# USB_Dongle_Parem.net
KiCad netlist of a schematic drawn in EAGLE
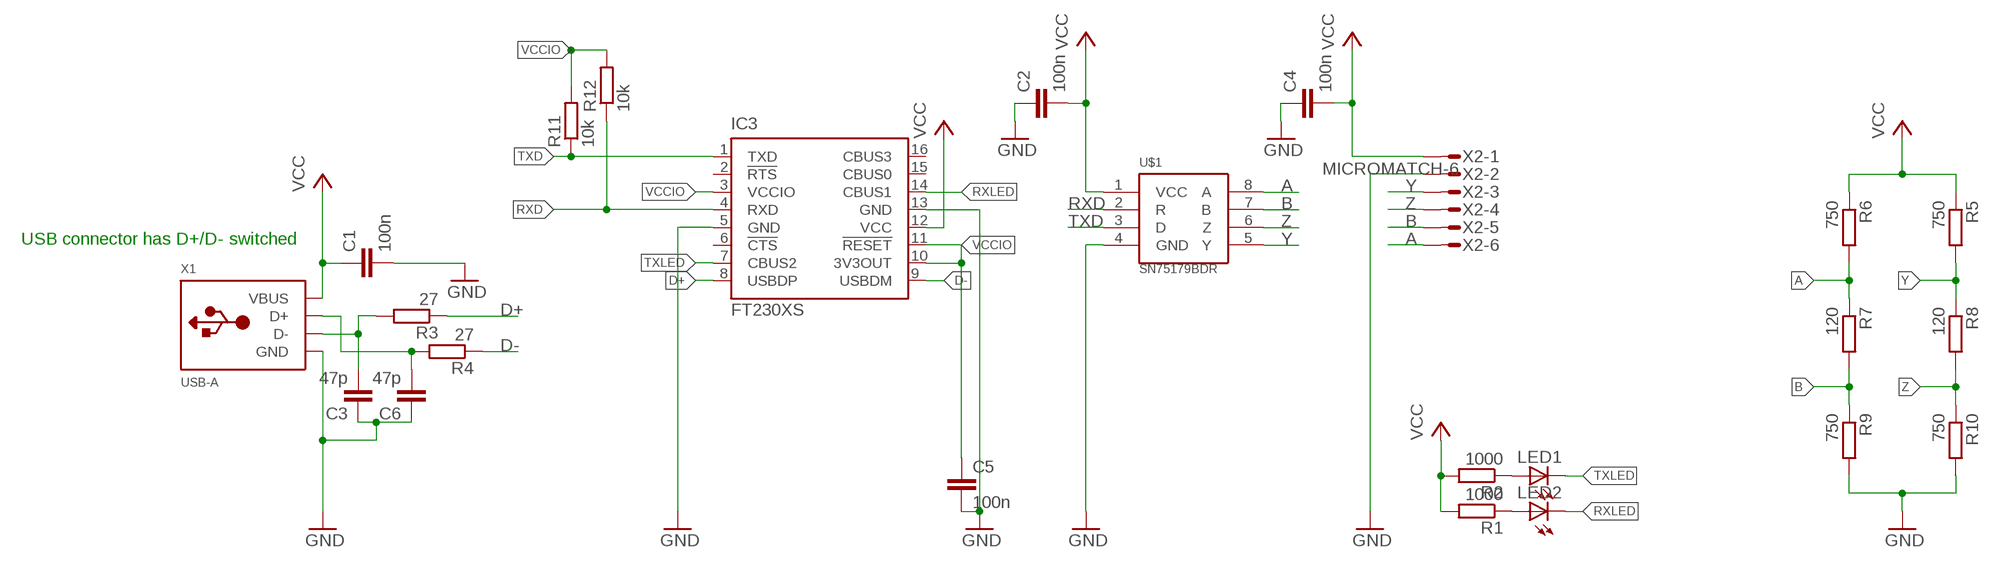
[diagram p0: schematic, sheet 1]

(export (version "E")
  (design (tool "Eeschema 10.0.6"))
  (components
    (comp (ref "C1")
      (value "100n")
      (footprint "eagle-import:C0603")
      (libsource (lib "eagle-import") (part "CC0603"))
    )
    (comp (ref "C2")
      (value "100n")
      (footprint "eagle-import:C0603")
      (libsource (lib "eagle-import") (part "CC0603"))
    )
    (comp (ref "C3")
      (value "47p")
      (footprint "eagle-import:C0603")
      (libsource (lib "eagle-import") (part "CC0603"))
    )
    (comp (ref "C4")
      (value "100n")
      (footprint "eagle-import:C0603")
      (libsource (lib "eagle-import") (part "CC0603"))
    )
    (comp (ref "C5")
      (value "100n")
      (footprint "eagle-import:C0603")
      (libsource (lib "eagle-import") (part "CC0603"))
    )
    (comp (ref "C6")
      (value "47p")
      (footprint "eagle-import:C0603")
      (libsource (lib "eagle-import") (part "CC0603"))
    )
    (comp (ref "IC3")
      (value "FT230XS")
      (footprint "eagle-import:SSOP16")
      (libsource (lib "eagle-import") (part "FT230XS"))
    )
    (comp (ref "LED1")
      (value "LED_ESML0603")
      (footprint "eagle-import:LED_SML0603")
      (libsource (lib "eagle-import") (part "LED_ESML0603"))
    )
    (comp (ref "LED2")
      (value "LED_ESML0603")
      (footprint "eagle-import:LED_SML0603")
      (libsource (lib "eagle-import") (part "LED_ESML0603"))
    )
    (comp (ref "R1")
      (value "1000")
      (footprint "eagle-import:R0603")
      (libsource (lib "eagle-import") (part "R-EU_R0603"))
    )
    (comp (ref "R2")
      (value "1000")
      (footprint "eagle-import:R0603")
      (libsource (lib "eagle-import") (part "R-EU_R0603"))
    )
    (comp (ref "R3")
      (value "27")
      (footprint "eagle-import:R0603")
      (libsource (lib "eagle-import") (part "R-EU_R0603"))
    )
    (comp (ref "R4")
      (value "27")
      (footprint "eagle-import:R0603")
      (libsource (lib "eagle-import") (part "R-EU_R0603"))
    )
    (comp (ref "R5")
      (value "750")
      (footprint "eagle-import:R0603")
      (libsource (lib "eagle-import") (part "R-EU_R0603"))
    )
    (comp (ref "R6")
      (value "750")
      (footprint "eagle-import:R0603")
      (libsource (lib "eagle-import") (part "R-EU_R0603"))
    )
    (comp (ref "R7")
      (value "120")
      (footprint "eagle-import:R0603")
      (libsource (lib "eagle-import") (part "R-EU_R0603"))
    )
    (comp (ref "R8")
      (value "120")
      (footprint "eagle-import:R0603")
      (libsource (lib "eagle-import") (part "R-EU_R0603"))
    )
    (comp (ref "R9")
      (value "750")
      (footprint "eagle-import:R0603")
      (libsource (lib "eagle-import") (part "R-EU_R0603"))
    )
    (comp (ref "R10")
      (value "750")
      (footprint "eagle-import:R0603")
      (libsource (lib "eagle-import") (part "R-EU_R0603"))
    )
    (comp (ref "R11")
      (value "10k")
      (footprint "eagle-import:R0603")
      (libsource (lib "eagle-import") (part "R-EU_R0603"))
    )
    (comp (ref "R12")
      (value "10k")
      (footprint "eagle-import:R0603")
      (libsource (lib "eagle-import") (part "R-EU_R0603"))
    )
    (comp (ref "U$1")
      (value "SN75179BDR")
      (footprint "eagle-import:SOIC8")
      (libsource (lib "eagle-import") (part "SN75179BDR"))
    )
    (comp (ref "X1")
      (value "USB-A")
      (footprint "eagle-import:MOLEX_480371000")
      (libsource (lib "eagle-import") (part "USB-A"))
    )
    (comp (ref "X2")
      (value "MICROMATCH-6")
      (footprint "eagle-import:MICROMATCH-6")
      (fields (field (name "MPN") "7-215464-6"))
      (libsource (lib "eagle-import") (part "MICROMATCH-6"))
    )
  )
  (nets
    (net (code "1") (name "A") (class "Default")
      (node (ref "R6") (pin "2") (pinfunction "2_2") (pintype "passive"))
      (node (ref "R7") (pin "1") (pinfunction "1_1") (pintype "passive"))
      (node (ref "U$1") (pin "8") (pinfunction "A_8") (pintype "bidirectional"))
      (node (ref "X2") (pin "6") (pinfunction "S_6") (pintype "passive"))
    )
    (net (code "2") (name "B") (class "Default")
      (node (ref "R7") (pin "2") (pinfunction "2_2") (pintype "passive"))
      (node (ref "R9") (pin "1") (pinfunction "1_1") (pintype "passive"))
      (node (ref "U$1") (pin "7") (pinfunction "B_7") (pintype "bidirectional"))
      (node (ref "X2") (pin "5") (pinfunction "S_5") (pintype "passive"))
    )
    (net (code "3") (name "D+") (class "Default")
      (node (ref "IC3") (pin "8") (pinfunction "USBDP_8") (pintype "input"))
      (node (ref "R3") (pin "1") (pinfunction "1_1") (pintype "passive"))
    )
    (net (code "4") (name "D-") (class "Default")
      (node (ref "IC3") (pin "9") (pinfunction "USBDM_9") (pintype "input"))
      (node (ref "R4") (pin "1") (pinfunction "1_1") (pintype "passive"))
    )
    (net (code "5") (name "GND") (class "Default")
      (node (ref "C1") (pin "2") (pinfunction "2_2") (pintype "passive"))
      (node (ref "C2") (pin "1") (pinfunction "1_1") (pintype "passive"))
      (node (ref "C3") (pin "1") (pinfunction "1_1") (pintype "passive"))
      (node (ref "C4") (pin "1") (pinfunction "1_1") (pintype "passive"))
      (node (ref "C5") (pin "2") (pinfunction "2_2") (pintype "passive"))
      (node (ref "C6") (pin "1") (pinfunction "1_1") (pintype "passive"))
      (node (ref "IC3") (pin "13") (pinfunction "GND_13") (pintype "power_in"))
      (node (ref "IC3") (pin "5") (pinfunction "GND_5") (pintype "power_in"))
      (node (ref "R10") (pin "2") (pinfunction "2_2") (pintype "passive"))
      (node (ref "R9") (pin "2") (pinfunction "2_2") (pintype "passive"))
      (node (ref "U$1") (pin "4") (pinfunction "GND_4") (pintype "bidirectional"))
      (node (ref "X1") (pin "4") (pinfunction "GND_4") (pintype "power_in"))
      (node (ref "X2") (pin "2") (pinfunction "S_2") (pintype "passive"))
    )
    (net (code "6") (name "Net-(LED1-PadA)") (class "Default")
      (node (ref "LED1") (pin "A") (pinfunction "A_A") (pintype "passive"))
      (node (ref "R2") (pin "1") (pinfunction "1_1") (pintype "passive"))
    )
    (net (code "7") (name "Net-(LED2-PadA)") (class "Default")
      (node (ref "LED2") (pin "A") (pinfunction "A_A") (pintype "passive"))
      (node (ref "R1") (pin "1") (pinfunction "1_1") (pintype "passive"))
    )
    (net (code "8") (name "Net-(X1-D+)") (class "Default")
      (node (ref "C6") (pin "2") (pinfunction "2_2") (pintype "passive"))
      (node (ref "R4") (pin "2") (pinfunction "2_2") (pintype "passive"))
      (node (ref "X1") (pin "3") (pinfunction "D+_3") (pintype "bidirectional"))
    )
    (net (code "9") (name "Net-(X1-D-)") (class "Default")
      (node (ref "C3") (pin "2") (pinfunction "2_2") (pintype "passive"))
      (node (ref "R3") (pin "2") (pinfunction "2_2") (pintype "passive"))
      (node (ref "X1") (pin "2") (pinfunction "D-_2") (pintype "bidirectional"))
    )
    (net (code "10") (name "RXD") (class "Default")
      (node (ref "IC3") (pin "4") (pinfunction "RXD_4") (pintype "input"))
      (node (ref "R12") (pin "1") (pinfunction "1_1") (pintype "passive"))
      (node (ref "U$1") (pin "2") (pinfunction "R_2") (pintype "bidirectional"))
    )
    (net (code "11") (name "RXLED") (class "Default")
      (node (ref "IC3") (pin "14") (pinfunction "CBUS1_14") (pintype "bidirectional"))
      (node (ref "LED2") (pin "C") (pinfunction "C_C") (pintype "passive"))
    )
    (net (code "12") (name "TXD") (class "Default")
      (node (ref "IC3") (pin "1") (pinfunction "TXD_1") (pintype "output"))
      (node (ref "R11") (pin "1") (pinfunction "1_1") (pintype "passive"))
      (node (ref "U$1") (pin "3") (pinfunction "D_3") (pintype "bidirectional"))
    )
    (net (code "13") (name "TXLED") (class "Default")
      (node (ref "IC3") (pin "7") (pinfunction "CBUS2_7") (pintype "bidirectional"))
      (node (ref "LED1") (pin "C") (pinfunction "C_C") (pintype "passive"))
    )
    (net (code "14") (name "VCC") (class "Default")
      (node (ref "C1") (pin "1") (pinfunction "1_1") (pintype "passive"))
      (node (ref "C2") (pin "2") (pinfunction "2_2") (pintype "passive"))
      (node (ref "C4") (pin "2") (pinfunction "2_2") (pintype "passive"))
      (node (ref "IC3") (pin "12") (pinfunction "VCC_12") (pintype "power_in"))
      (node (ref "R1") (pin "2") (pinfunction "2_2") (pintype "passive"))
      (node (ref "R2") (pin "2") (pinfunction "2_2") (pintype "passive"))
      (node (ref "R5") (pin "1") (pinfunction "1_1") (pintype "passive"))
      (node (ref "R6") (pin "1") (pinfunction "1_1") (pintype "passive"))
      (node (ref "U$1") (pin "1") (pinfunction "VCC_1") (pintype "bidirectional"))
      (node (ref "X1") (pin "1") (pinfunction "VBUS_1") (pintype "power_in"))
      (node (ref "X2") (pin "1") (pinfunction "S_1") (pintype "passive"))
    )
    (net (code "15") (name "VCCIO") (class "Default")
      (node (ref "C5") (pin "1") (pinfunction "1_1") (pintype "passive"))
      (node (ref "IC3") (pin "10") (pinfunction "3V3OUT_10") (pintype "output"))
      (node (ref "IC3") (pin "11") (pinfunction "~{RESET}_11") (pintype "input"))
      (node (ref "IC3") (pin "3") (pinfunction "VCCIO_3") (pintype "power_in"))
      (node (ref "R11") (pin "2") (pinfunction "2_2") (pintype "passive"))
      (node (ref "R12") (pin "2") (pinfunction "2_2") (pintype "passive"))
    )
    (net (code "16") (name "Y") (class "Default")
      (node (ref "R5") (pin "2") (pinfunction "2_2") (pintype "passive"))
      (node (ref "R8") (pin "1") (pinfunction "1_1") (pintype "passive"))
      (node (ref "U$1") (pin "5") (pinfunction "Y_5") (pintype "bidirectional"))
      (node (ref "X2") (pin "3") (pinfunction "S_3") (pintype "passive"))
    )
    (net (code "17") (name "Z") (class "Default")
      (node (ref "R10") (pin "1") (pinfunction "1_1") (pintype "passive"))
      (node (ref "R8") (pin "2") (pinfunction "2_2") (pintype "passive"))
      (node (ref "U$1") (pin "6") (pinfunction "Z_6") (pintype "bidirectional"))
      (node (ref "X2") (pin "4") (pinfunction "S_4") (pintype "passive"))
    )
    (net (code "18") (name "unconnected-(IC3-CBUS0-Pad15)") (class "Default")
      (node (ref "IC3") (pin "15") (pinfunction "CBUS0_15") (pintype "bidirectional"))
    )
    (net (code "19") (name "unconnected-(IC3-CBUS3-Pad16)") (class "Default")
      (node (ref "IC3") (pin "16") (pinfunction "CBUS3_16") (pintype "bidirectional"))
    )
    (net (code "20") (name "unconnected-(IC3-~{CTS}-Pad6)") (class "Default")
      (node (ref "IC3") (pin "6") (pinfunction "~{CTS}_6") (pintype "input"))
    )
    (net (code "21") (name "unconnected-(IC3-~{RTS}-Pad2)") (class "Default")
      (node (ref "IC3") (pin "2") (pinfunction "~{RTS}_2") (pintype "output"))
    )
  )
)
